# SOT-23.net
KiCad netlist of a schematic drawn in EAGLE
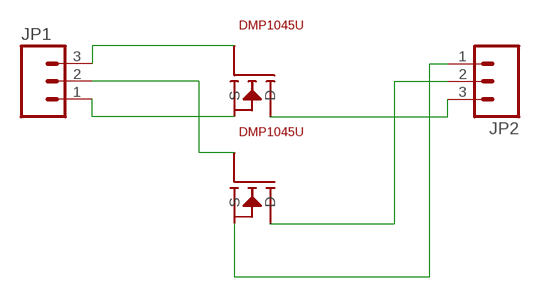
[diagram p0: schematic, sheet 1]

(export (version "E")
  (design (tool "Eeschema 10.0.6"))
  (components
    (comp (ref "JP1")
      (value "M03LOCK")
      (footprint "eagle-import:1X03_LOCK")
      (libsource (lib "eagle-import") (part "M03LOCK"))
    )
    (comp (ref "JP2")
      (value "M03LOCK")
      (footprint "eagle-import:1X03_LOCK")
      (libsource (lib "eagle-import") (part "M03LOCK"))
    )
    (comp (ref "U$1")
      (value "DMP1045U")
      (footprint "eagle-import:SOT-23")
      (libsource (lib "eagle-import") (part "DMP1045U"))
    )
    (comp (ref "U$2")
      (value "DMP1045U")
      (footprint "eagle-import:SOT-23")
      (libsource (lib "eagle-import") (part "DMP1045U"))
    )
  )
  (nets
    (net (code "1") (name "Net-(U$1-D)") (class "Default")
      (node (ref "JP2") (pin "3") (pinfunction "3_3") (pintype "passive"))
      (node (ref "U$1") (pin "3") (pinfunction "D_3") (pintype "power_in"))
    )
    (net (code "2") (name "Net-(U$1-G)") (class "Default")
      (node (ref "JP1") (pin "3") (pinfunction "3_3") (pintype "passive"))
      (node (ref "U$1") (pin "1") (pinfunction "G_1") (pintype "power_in"))
    )
    (net (code "3") (name "Net-(U$1-S)") (class "Default")
      (node (ref "JP1") (pin "1") (pinfunction "1_1") (pintype "passive"))
      (node (ref "U$1") (pin "2") (pinfunction "S_2") (pintype "power_in"))
    )
    (net (code "4") (name "Net-(U$2-D)") (class "Default")
      (node (ref "JP2") (pin "2") (pinfunction "2_2") (pintype "passive"))
      (node (ref "U$2") (pin "3") (pinfunction "D_3") (pintype "power_in"))
    )
    (net (code "5") (name "Net-(U$2-G)") (class "Default")
      (node (ref "JP1") (pin "2") (pinfunction "2_2") (pintype "passive"))
      (node (ref "U$2") (pin "1") (pinfunction "G_1") (pintype "power_in"))
    )
    (net (code "6") (name "Net-(U$2-S)") (class "Default")
      (node (ref "JP2") (pin "1") (pinfunction "1_1") (pintype "passive"))
      (node (ref "U$2") (pin "2") (pinfunction "S_2") (pintype "power_in"))
    )
  )
)
